# CBV2.net
KiCad netlist of a schematic drawn in EAGLE
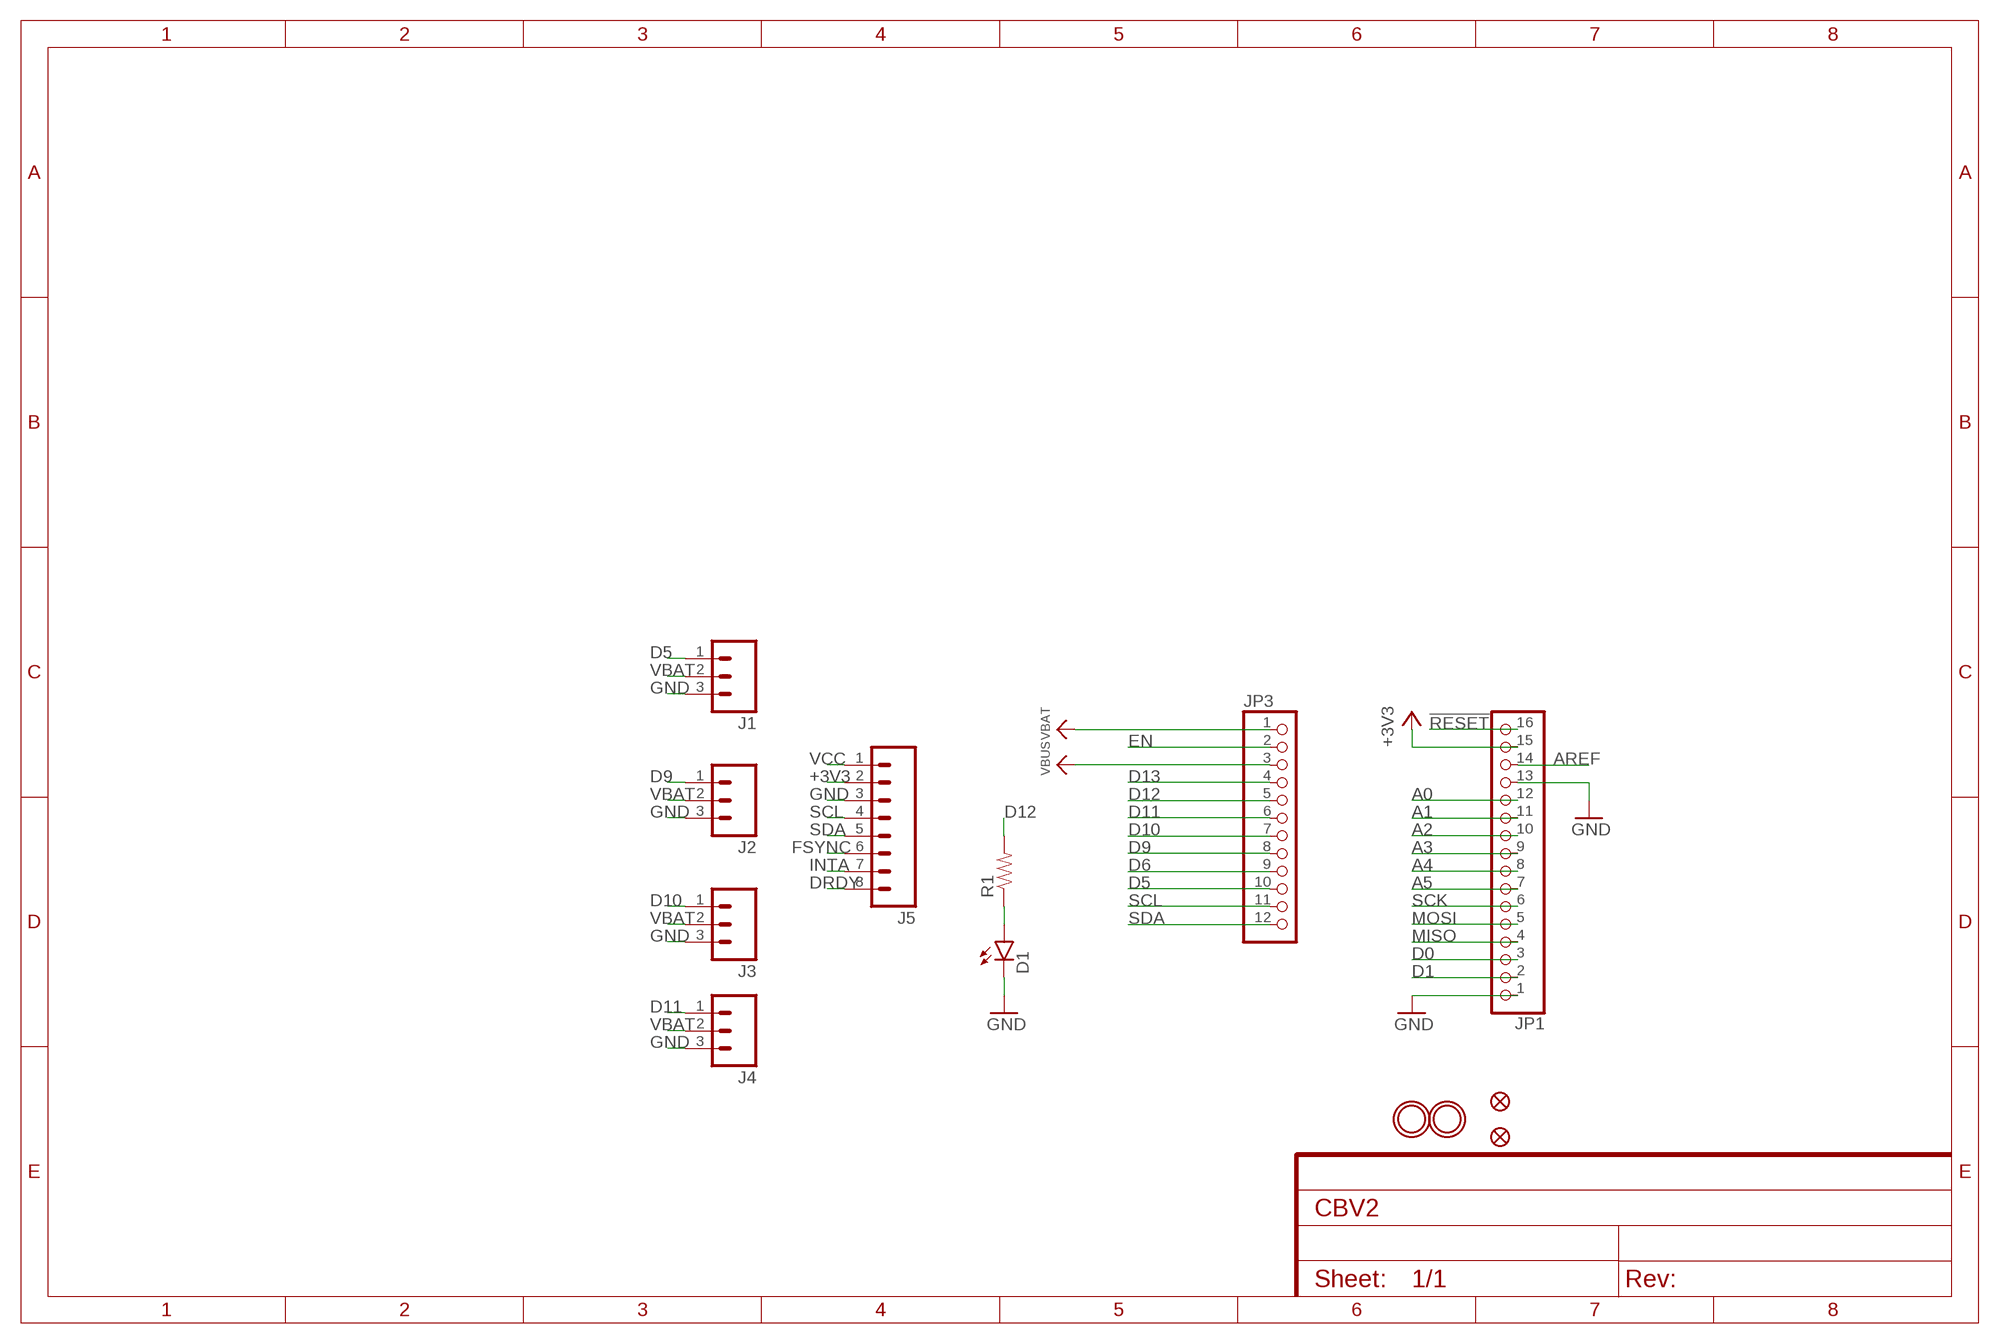
[diagram p0: schematic, sheet 1]

(export (version "E")
  (design (tool "Eeschema 10.0.6"))
  (components
    (comp (ref "D1")
      (value "LED3MM")
      (footprint "eagle-import:LED3MM")
      (libsource (lib "eagle-import") (part "LED3MM"))
    )
    (comp (ref "J1")
      (value "M03PTH")
      (footprint "eagle-import:1X03")
      (libsource (lib "eagle-import") (part "M03PTH"))
    )
    (comp (ref "J2")
      (value "M03PTH")
      (footprint "eagle-import:1X03")
      (libsource (lib "eagle-import") (part "M03PTH"))
    )
    (comp (ref "J3")
      (value "M03PTH")
      (footprint "eagle-import:1X03")
      (libsource (lib "eagle-import") (part "M03PTH"))
    )
    (comp (ref "J4")
      (value "M03PTH")
      (footprint "eagle-import:1X03")
      (libsource (lib "eagle-import") (part "M03PTH"))
    )
    (comp (ref "J5")
      (value "M08")
      (footprint "eagle-import:1X08_ROUND")
      (libsource (lib "eagle-import") (part "M08"))
    )
    (comp (ref "JP1")
      (value "HEADER-1X16ROUND")
      (footprint "eagle-import:1X16_ROUND")
      (libsource (lib "eagle-import") (part "HEADER-1X16ROUND"))
    )
    (comp (ref "JP3")
      (value "HEADER-1X12")
      (footprint "eagle-import:1X12_ROUND")
      (libsource (lib "eagle-import") (part "HEADER-1X12"))
    )
    (comp (ref "R1")
      (value "RESISTORPTH-1/4W")
      (footprint "eagle-import:AXIAL-0.4")
      (libsource (lib "eagle-import") (part "RESISTORPTH-1/4W"))
    )
    (comp (ref "U$31")
      (value "MOUNTINGHOLE2.5")
      (footprint "eagle-import:MOUNTINGHOLE_2.5_PLATED")
      (libsource (lib "eagle-import") (part "MOUNTINGHOLE2.5"))
    )
    (comp (ref "U$32")
      (value "MOUNTINGHOLE2.5")
      (footprint "eagle-import:MOUNTINGHOLE_2.5_PLATED")
      (libsource (lib "eagle-import") (part "MOUNTINGHOLE2.5"))
    )
    (comp (ref "U$34")
      (value "FIDUCIAL\"\"")
      (footprint "eagle-import:FIDUCIAL_1MM")
      (libsource (lib "eagle-import") (part "FIDUCIAL{dblquote}{dblquote}"))
    )
    (comp (ref "U$35")
      (value "FIDUCIAL\"\"")
      (footprint "eagle-import:FIDUCIAL_1MM")
      (libsource (lib "eagle-import") (part "FIDUCIAL{dblquote}{dblquote}"))
    )
  )
  (nets
    (net (code "1") (name "+3V3") (class "Default")
      (node (ref "J5") (pin "2") (pinfunction "2_2") (pintype "passive"))
      (node (ref "JP1") (pin "15") (pinfunction "15_15") (pintype "passive"))
    )
    (net (code "2") (name "/A0") (class "Default")
      (node (ref "JP1") (pin "12") (pinfunction "12_12") (pintype "passive"))
    )
    (net (code "3") (name "/A1") (class "Default")
      (node (ref "JP1") (pin "11") (pinfunction "11_11") (pintype "passive"))
    )
    (net (code "4") (name "/A2") (class "Default")
      (node (ref "JP1") (pin "10") (pinfunction "10_10") (pintype "passive"))
    )
    (net (code "5") (name "/A3") (class "Default")
      (node (ref "JP1") (pin "9") (pinfunction "9_9") (pintype "passive"))
    )
    (net (code "6") (name "/A4") (class "Default")
      (node (ref "JP1") (pin "8") (pinfunction "8_8") (pintype "passive"))
    )
    (net (code "7") (name "/A5") (class "Default")
      (node (ref "JP1") (pin "7") (pinfunction "7_7") (pintype "passive"))
    )
    (net (code "8") (name "/AREF") (class "Default")
      (node (ref "JP1") (pin "14") (pinfunction "14_14") (pintype "passive"))
    )
    (net (code "9") (name "/D0") (class "Default")
      (node (ref "JP1") (pin "3") (pinfunction "3_3") (pintype "passive"))
    )
    (net (code "10") (name "/D1") (class "Default")
      (node (ref "JP1") (pin "2") (pinfunction "2_2") (pintype "passive"))
    )
    (net (code "11") (name "/D5") (class "Default")
      (node (ref "J1") (pin "1") (pinfunction "1_1") (pintype "passive"))
      (node (ref "JP3") (pin "10") (pinfunction "10_10") (pintype "passive"))
    )
    (net (code "12") (name "/D6") (class "Default")
      (node (ref "JP3") (pin "9") (pinfunction "9_9") (pintype "passive"))
    )
    (net (code "13") (name "/D9") (class "Default")
      (node (ref "J2") (pin "1") (pinfunction "1_1") (pintype "passive"))
      (node (ref "JP3") (pin "8") (pinfunction "8_8") (pintype "passive"))
    )
    (net (code "14") (name "/D10") (class "Default")
      (node (ref "J3") (pin "1") (pinfunction "1_1") (pintype "passive"))
      (node (ref "JP3") (pin "7") (pinfunction "7_7") (pintype "passive"))
    )
    (net (code "15") (name "/D11") (class "Default")
      (node (ref "J4") (pin "1") (pinfunction "1_1") (pintype "passive"))
      (node (ref "JP3") (pin "6") (pinfunction "6_6") (pintype "passive"))
    )
    (net (code "16") (name "/D12") (class "Default")
      (node (ref "JP3") (pin "5") (pinfunction "5_5") (pintype "passive"))
      (node (ref "R1") (pin "P$2") (pinfunction "2_P$2") (pintype "passive"))
    )
    (net (code "17") (name "/D13") (class "Default")
      (node (ref "JP3") (pin "4") (pinfunction "4_4") (pintype "passive"))
    )
    (net (code "18") (name "/DRDY") (class "Default")
      (node (ref "J5") (pin "8") (pinfunction "8_8") (pintype "passive"))
    )
    (net (code "19") (name "/EN") (class "Default")
      (node (ref "JP3") (pin "2") (pinfunction "2_2") (pintype "passive"))
    )
    (net (code "20") (name "/FSYNC") (class "Default")
      (node (ref "J5") (pin "6") (pinfunction "6_6") (pintype "passive"))
    )
    (net (code "21") (name "/INTA") (class "Default")
      (node (ref "J5") (pin "7") (pinfunction "7_7") (pintype "passive"))
    )
    (net (code "22") (name "/MISO") (class "Default")
      (node (ref "JP1") (pin "4") (pinfunction "4_4") (pintype "passive"))
    )
    (net (code "23") (name "/MOSI") (class "Default")
      (node (ref "JP1") (pin "5") (pinfunction "5_5") (pintype "passive"))
    )
    (net (code "24") (name "/SCK") (class "Default")
      (node (ref "JP1") (pin "6") (pinfunction "6_6") (pintype "passive"))
    )
    (net (code "25") (name "/SCL") (class "Default")
      (node (ref "J5") (pin "4") (pinfunction "4_4") (pintype "passive"))
      (node (ref "JP3") (pin "11") (pinfunction "11_11") (pintype "passive"))
    )
    (net (code "26") (name "/SDA") (class "Default")
      (node (ref "J5") (pin "5") (pinfunction "5_5") (pintype "passive"))
      (node (ref "JP3") (pin "12") (pinfunction "12_12") (pintype "passive"))
    )
    (net (code "27") (name "/VCC") (class "Default")
      (node (ref "J5") (pin "1") (pinfunction "1_1") (pintype "passive"))
    )
    (net (code "28") (name "/~{RESET}") (class "Default")
      (node (ref "JP1") (pin "16") (pinfunction "16_16") (pintype "passive"))
    )
    (net (code "29") (name "GND") (class "Default")
      (node (ref "D1") (pin "K") (pinfunction "C_K") (pintype "passive"))
      (node (ref "J1") (pin "3") (pinfunction "3_3") (pintype "passive"))
      (node (ref "J2") (pin "3") (pinfunction "3_3") (pintype "passive"))
      (node (ref "J3") (pin "3") (pinfunction "3_3") (pintype "passive"))
      (node (ref "J4") (pin "3") (pinfunction "3_3") (pintype "passive"))
      (node (ref "J5") (pin "3") (pinfunction "3_3") (pintype "passive"))
      (node (ref "JP1") (pin "1") (pinfunction "1_1") (pintype "passive"))
      (node (ref "JP1") (pin "13") (pinfunction "13_13") (pintype "passive"))
    )
    (net (code "30") (name "Net-(R1-1)") (class "Default")
      (node (ref "D1") (pin "A") (pinfunction "A_A") (pintype "passive"))
      (node (ref "R1") (pin "P$1") (pinfunction "1_P$1") (pintype "passive"))
    )
    (net (code "31") (name "VBAT") (class "Default")
      (node (ref "J1") (pin "2") (pinfunction "2_2") (pintype "passive"))
      (node (ref "J2") (pin "2") (pinfunction "2_2") (pintype "passive"))
      (node (ref "J3") (pin "2") (pinfunction "2_2") (pintype "passive"))
      (node (ref "J4") (pin "2") (pinfunction "2_2") (pintype "passive"))
      (node (ref "JP3") (pin "1") (pinfunction "1_1") (pintype "passive"))
    )
    (net (code "32") (name "VBUS") (class "Default")
      (node (ref "JP3") (pin "3") (pinfunction "3_3") (pintype "passive"))
    )
  )
)
